# MCU_Circuit.net
KiCad netlist of a schematic drawn in Altium Designer
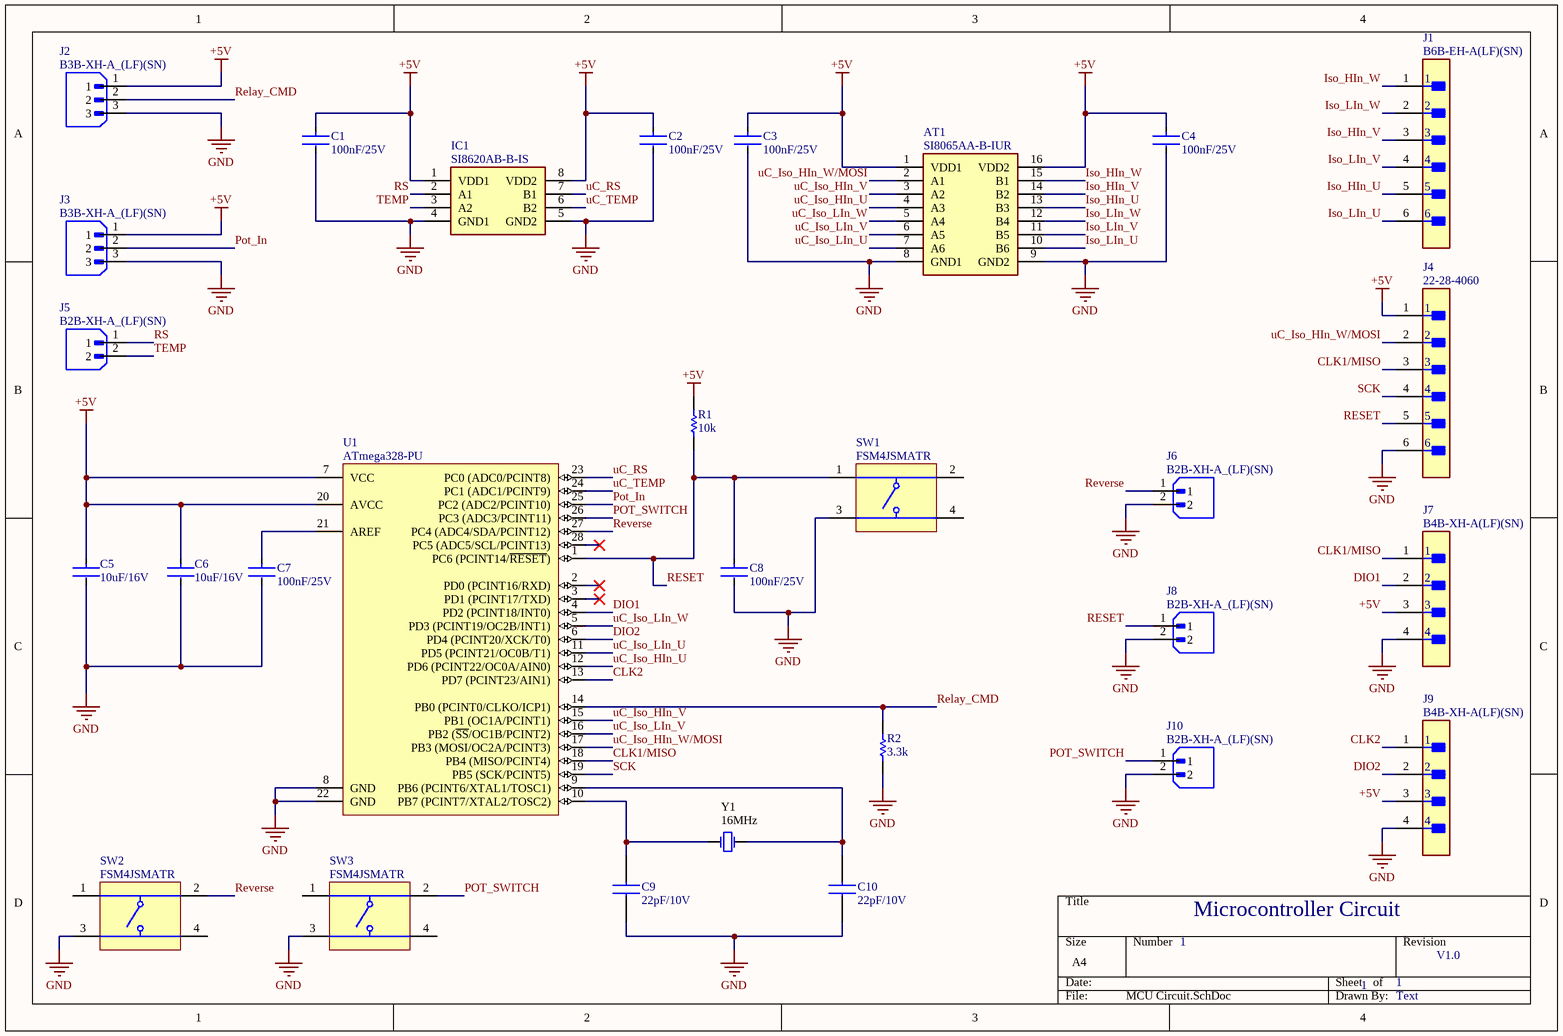
[diagram p0: MCU Circuit.SchDoc]

(export (version "E")
  (design (tool "Eeschema 10.0.6"))
  (components
    (comp (ref "AT1")
      (value "SI8065AA-B-IUR")
      (footprint "SamacSys:SOP64P600X175-16N")
      (description "Attenuator or Isolator")
      (fields (field (name "MOUSER PART NUMBER") "634-SI8065AA-B-IUR"))
      (libsource (lib "*") (part "SI8065AA-B-IUR"))
    )
    (comp (ref "C1")
      (value "100nF/25V")
      (footprint "FP-1210-L_3_3_0_4-W_2_5_0-MFG")
      (description "General Purpose Ceramic Capacitor, 1210, 100nF, 10%, X7R, +15%, 50V")
      (fields (field (name "TOLERANCE") "10%") (field (name "VOLTAGE") "50V"))
      (libsource (lib "Altium Content Vault") (part "b4654b650e69147ec39a6b967a45e02"))
    )
    (comp (ref "C2")
      (value "100nF/25V")
      (footprint "FP-1210-L_3_3_0_4-W_2_5_0-MFG")
      (description "General Purpose Ceramic Capacitor, 1210, 100nF, 10%, X7R, +15%, 50V")
      (fields (field (name "TOLERANCE") "10%") (field (name "VOLTAGE") "50V"))
      (libsource (lib "Altium Content Vault") (part "b4654b650e69147ec39a6b967a45e02"))
    )
    (comp (ref "C3")
      (value "100nF/25V")
      (footprint "FP-1210-L_3_3_0_4-W_2_5_0-MFG")
      (description "General Purpose Ceramic Capacitor, 1210, 100nF, 10%, X7R, +15%, 50V")
      (fields (field (name "TOLERANCE") "10%") (field (name "VOLTAGE") "50V"))
      (libsource (lib "Altium Content Vault") (part "b4654b650e69147ec39a6b967a45e02"))
    )
    (comp (ref "C4")
      (value "100nF/25V")
      (footprint "FP-1210-L_3_3_0_4-W_2_5_0-MFG")
      (description "General Purpose Ceramic Capacitor, 1210, 100nF, 10%, X7R, +15%, 50V")
      (fields (field (name "TOLERANCE") "10%") (field (name "VOLTAGE") "50V"))
      (libsource (lib "Altium Content Vault") (part "b4654b650e69147ec39a6b967a45e02"))
    )
    (comp (ref "C5")
      (value "10uF/16V")
      (footprint "FP-1206-L_3_2_0_2-W_1_6_0-IPC_A")
      (description "General Purpose Ceramic Capacitor, 1206, 10uF, 10%, X5R, 15%, 10V")
      (fields (field (name "TOLERANCE") "10%") (field (name "VOLTAGE") "10V"))
      (libsource (lib "Altium Content Vault") (part "02cd4be3c70576c341d710602a673aa"))
    )
    (comp (ref "C6")
      (value "10uF/16V")
      (footprint "FP-1206-L_3_2_0_2-W_1_6_0-IPC_A")
      (description "General Purpose Ceramic Capacitor, 1206, 10uF, 10%, X5R, 15%, 10V")
      (fields (field (name "TOLERANCE") "10%") (field (name "VOLTAGE") "10V"))
      (libsource (lib "Altium Content Vault") (part "02cd4be3c70576c341d710602a673aa"))
    )
    (comp (ref "C7")
      (value "100nF/25V")
      (footprint "FP-1210-L_3_3_0_4-W_2_5_0-MFG")
      (description "General Purpose Ceramic Capacitor, 1210, 100nF, 10%, X7R, +15%, 50V")
      (fields (field (name "TOLERANCE") "10%") (field (name "VOLTAGE") "50V"))
      (libsource (lib "Altium Content Vault") (part "b4654b650e69147ec39a6b967a45e02"))
    )
    (comp (ref "C8")
      (value "100nF/25V")
      (footprint "FP-1210-L_3_3_0_4-W_2_5_0-MFG")
      (description "General Purpose Ceramic Capacitor, 1210, 100nF, 10%, X7R, +15%, 50V")
      (fields (field (name "TOLERANCE") "10%") (field (name "VOLTAGE") "50V"))
      (libsource (lib "Altium Content Vault") (part "b4654b650e69147ec39a6b967a45e02"))
    )
    (comp (ref "C9")
      (value "22pF/10V")
      (footprint "SamacSys:CAPC3216X90N")
      (description "Capacitor")
      (fields
        (field (name "MANUFACTURER_PART_NUMBER") "885012008002")
        (field (name "MOUSER PART NUMBER") "710-885012008002")
      )
      (libsource (lib "*") (part "885012008002"))
    )
    (comp (ref "C10")
      (value "22pF/10V")
      (footprint "SamacSys:CAPC3216X90N")
      (description "Capacitor")
      (fields
        (field (name "MANUFACTURER_PART_NUMBER") "885012008002")
        (field (name "MOUSER PART NUMBER") "710-885012008002")
      )
      (libsource (lib "*") (part "885012008002"))
    )
    (comp (ref "IC1")
      (value "SI8620AB-B-IS")
      (footprint "SamacSys:SOIC127P600X175-8N")
      (description "Integrated Circuit")
      (fields (field (name "MOUSER PART NUMBER") "634-SI8620AB-B-IS"))
      (libsource (lib "*") (part "SI8620AB-B-IS"))
    )
    (comp (ref "J1")
      (value "B6B-EH-A(LF)(SN)")
      (footprint "FP-B6B-EH-A_LF_SN-MFG")
      (description "CONN HEADER VERT 6POS 2.5MM")
      (libsource (lib "Altium Content Vault") (part "f2cb566baf1c37ab5a3b8e90bbeafd6"))
    )
    (comp (ref "J2")
      (value "B3B-XH-A_(LF)(SN)")
      (footprint "JST_B3B-XH-A (LF)(SN)")
      (description "Connector Header Through Hole 3 position 0.098 (2.50mm)")
      (fields (field (name "MF") "JST Sales America Inc.") (field (name "MP") "B3B-XH-A (LF)(SN)"))
      (libsource (lib "B3B-XH-A__LF__SN_") (part "B3B-XH-A_(LF)(SN)"))
    )
    (comp (ref "J3")
      (value "B3B-XH-A_(LF)(SN)")
      (footprint "JST_B3B-XH-A (LF)(SN)")
      (description "Connector Header Through Hole 3 position 0.098 (2.50mm)")
      (fields (field (name "MF") "JST Sales America Inc.") (field (name "MP") "B3B-XH-A (LF)(SN)"))
      (libsource (lib "B3B-XH-A__LF__SN_") (part "B3B-XH-A_(LF)(SN)"))
    )
    (comp (ref "J4")
      (value "22-28-4060")
      (footprint "FP-22-28-4060-MFG")
      (description "CONN HEADER VERT 6POS 2.54MM")
      (libsource (lib "Altium Content Vault") (part "f2cb566baf1c37ab5a3b8e90bbeafd6"))
    )
    (comp (ref "J5")
      (value "B2B-XH-A_(LF)(SN)")
      (footprint "JST_B2B-XH-A_(LF)(SN)")
      (description "Connector Header Through Hole 2 position 0.098 (2.50mm)")
      (fields (field (name "MF") "JST Sales") (field (name "MP") "B2B-XH-A (LF)(SN)"))
      (libsource (lib "") (part "B2B-XH-A_(LF)(SN)_1"))
    )
    (comp (ref "J6")
      (value "B2B-XH-A_(LF)(SN)")
      (footprint "JST_B2B-XH-A_(LF)(SN)")
      (description "Connector Header Through Hole 2 position 0.098 (2.50mm)")
      (fields (field (name "MF") "JST Sales") (field (name "MP") "B2B-XH-A (LF)(SN)"))
      (libsource (lib "B2B-XH-A__LF__SN_") (part "B2B-XH-A_(LF)(SN)"))
    )
    (comp (ref "J7")
      (value "B4B-XH-A(LF)(SN)")
      (footprint "FP-B4B-XH-A_LF_SN-MFG")
      (description "CONN HEADER VERT 4POS 2.5MM")
      (libsource (lib "Altium Content Vault") (part "299a8cea1bdcbc3624fe62c390fa72c"))
    )
    (comp (ref "J8")
      (value "B2B-XH-A_(LF)(SN)")
      (footprint "JST_B2B-XH-A_(LF)(SN)")
      (description "Connector Header Through Hole 2 position 0.098 (2.50mm)")
      (fields (field (name "MF") "JST Sales") (field (name "MP") "B2B-XH-A (LF)(SN)"))
      (libsource (lib "B2B-XH-A__LF__SN_") (part "B2B-XH-A_(LF)(SN)"))
    )
    (comp (ref "J9")
      (value "B4B-XH-A(LF)(SN)")
      (footprint "FP-B4B-XH-A_LF_SN-MFG")
      (description "CONN HEADER VERT 4POS 2.5MM")
      (libsource (lib "Altium Content Vault") (part "299a8cea1bdcbc3624fe62c390fa72c"))
    )
    (comp (ref "J10")
      (value "B2B-XH-A_(LF)(SN)")
      (footprint "JST_B2B-XH-A_(LF)(SN)")
      (description "Connector Header Through Hole 2 position 0.098 (2.50mm)")
      (fields (field (name "MF") "JST Sales") (field (name "MP") "B2B-XH-A (LF)(SN)"))
      (libsource (lib "B2B-XH-A__LF__SN_") (part "B2B-XH-A_(LF)(SN)"))
    )
    (comp (ref "R1")
      (value "10k")
      (footprint "RESC3225X70X50NL20T20")
      (description "1210")
      (fields (field (name "PART NUMBER") "ERJ-L14KF10CU") (field (name "MANUFACTURER") "Panasonic"))
      (libsource (lib "Altium Content Vault") (part "RES"))
    )
    (comp (ref "R2")
      (value "3.3k")
      (footprint "RESC3225X70X50NL20T20")
      (description "3.3k 0.5W 1210 SMD Resistor")
      (fields (field (name "PART NUMBER") "ERJ-L14KF10CU") (field (name "MANUFACTURER") "Panasonic"))
      (libsource (lib "Altium Content Vault") (part "RES"))
    )
    (comp (ref "SW1")
      (value "FSM4JSMATR")
      (footprint "TECO-FSM4JSMATR_V")
      (description "Micro Miniature Push Button Switch FSM JSM, 50 mA, -35 to 85 degC, 4-Pin SMD, RoHS, Tape and Reel")
      (fields (field (name "MANUFACTURER") "TE Connectivity"))
      (libsource (lib "Altium Content Vault") (part "SW-SPST-4_A"))
    )
    (comp (ref "SW2")
      (value "FSM4JSMATR")
      (footprint "TECO-FSM4JSMATR_V")
      (description "Micro Miniature Push Button Switch FSM JSM, 50 mA, -35 to 85 degC, 4-Pin SMD, RoHS, Tape and Reel")
      (fields (field (name "MANUFACTURER") "TE Connectivity"))
      (libsource (lib "Altium Content Vault") (part "SW-SPST-4_A"))
    )
    (comp (ref "SW3")
      (value "FSM4JSMATR")
      (footprint "TECO-FSM4JSMATR_V")
      (description "Micro Miniature Push Button Switch FSM JSM, 50 mA, -35 to 85 degC, 4-Pin SMD, RoHS, Tape and Reel")
      (fields (field (name "MANUFACTURER") "TE Connectivity"))
      (libsource (lib "Altium Content Vault") (part "SW-SPST-4_A"))
    )
    (comp (ref "U1")
      (value "ATmega328-PU")
      (footprint "28P3")
      (libsource (lib "Altium Content Vault") (part "MC-8B-ATM48-IL28"))
    )
    (comp (ref "Y1")
      (value "16MHz")
      (footprint "FOX-FOXSLF160-20")
      (description "Resistance Weld Thru-Hole Crystal, 16 MHz, -20 to 70 degC, 2-Pin THD, RoHS, Bulk")
      (fields (field (name "TOLERANCE") "1%"))
      (libsource (lib "Altium Content Vault") (part "XTAL-1-2-2"))
    )
  )
  (nets
    (net (code "1") (name "+5V") (class "Default")
      (node (ref "AT1") (pin "1") (pinfunction "VDD1_1") (pintype "passive"))
      (node (ref "AT1") (pin "16") (pinfunction "VDD2_16") (pintype "passive"))
      (node (ref "C1") (pin "1") (pinfunction "1_1") (pintype "passive"))
      (node (ref "C2") (pin "1") (pinfunction "1_1") (pintype "passive"))
      (node (ref "C3") (pin "1") (pinfunction "1_1") (pintype "passive"))
      (node (ref "C4") (pin "1") (pinfunction "1_1") (pintype "passive"))
      (node (ref "C5") (pin "1") (pinfunction "1_1") (pintype "passive"))
      (node (ref "C6") (pin "1") (pinfunction "1_1") (pintype "passive"))
      (node (ref "IC1") (pin "1") (pinfunction "VDD1_1") (pintype "passive"))
      (node (ref "IC1") (pin "8") (pinfunction "VDD2_8") (pintype "passive"))
      (node (ref "J2") (pin "1") (pinfunction "1_1") (pintype "passive"))
      (node (ref "J3") (pin "1") (pinfunction "1_1") (pintype "passive"))
      (node (ref "J4") (pin "1") (pinfunction "1_1") (pintype "passive"))
      (node (ref "J7") (pin "3") (pinfunction "3_3") (pintype "passive"))
      (node (ref "J9") (pin "3") (pinfunction "3_3") (pintype "passive"))
      (node (ref "R1") (pin "2") (pinfunction "2_2") (pintype "passive"))
      (node (ref "U1") (pin "20") (pinfunction "AVCC_20") (pintype "power_in"))
      (node (ref "U1") (pin "7") (pinfunction "VCC_7") (pintype "power_in"))
    )
    (net (code "2") (name "/CLK1{slash}MISO") (class "Default")
      (node (ref "J4") (pin "3") (pinfunction "3_3") (pintype "passive"))
      (node (ref "J7") (pin "1") (pinfunction "1_1") (pintype "passive"))
      (node (ref "U1") (pin "18") (pinfunction "PB4_(MISO/PCINT4)_18") (pintype "bidirectional"))
    )
    (net (code "3") (name "/CLK2") (class "Default")
      (node (ref "J9") (pin "1") (pinfunction "1_1") (pintype "passive"))
      (node (ref "U1") (pin "13") (pinfunction "PD7_(PCINT23/AIN1)_13") (pintype "bidirectional"))
    )
    (net (code "4") (name "/DIO1") (class "Default")
      (node (ref "J7") (pin "2") (pinfunction "2_2") (pintype "passive"))
      (node (ref "U1") (pin "4") (pinfunction "PD2_(PCINT18/INT0)_4") (pintype "bidirectional"))
    )
    (net (code "5") (name "/DIO2") (class "Default")
      (node (ref "J9") (pin "2") (pinfunction "2_2") (pintype "passive"))
      (node (ref "U1") (pin "6") (pinfunction "PD4_(PCINT20/XCK/T0)_6") (pintype "bidirectional"))
    )
    (net (code "6") (name "/Iso_HIn_U") (class "Default")
      (node (ref "AT1") (pin "13") (pinfunction "B3_13") (pintype "passive"))
      (node (ref "J1") (pin "5") (pinfunction "5_5") (pintype "passive"))
    )
    (net (code "7") (name "/Iso_HIn_V") (class "Default")
      (node (ref "AT1") (pin "14") (pinfunction "B2_14") (pintype "passive"))
      (node (ref "J1") (pin "3") (pinfunction "3_3") (pintype "passive"))
    )
    (net (code "8") (name "/Iso_HIn_W") (class "Default")
      (node (ref "AT1") (pin "15") (pinfunction "B1_15") (pintype "passive"))
      (node (ref "J1") (pin "1") (pinfunction "1_1") (pintype "passive"))
    )
    (net (code "9") (name "/Iso_LIn_U") (class "Default")
      (node (ref "AT1") (pin "10") (pinfunction "B6_10") (pintype "passive"))
      (node (ref "J1") (pin "6") (pinfunction "6_6") (pintype "passive"))
    )
    (net (code "10") (name "/Iso_LIn_V") (class "Default")
      (node (ref "AT1") (pin "11") (pinfunction "B5_11") (pintype "passive"))
      (node (ref "J1") (pin "4") (pinfunction "4_4") (pintype "passive"))
    )
    (net (code "11") (name "/Iso_LIn_W") (class "Default")
      (node (ref "AT1") (pin "12") (pinfunction "B4_12") (pintype "passive"))
      (node (ref "J1") (pin "2") (pinfunction "2_2") (pintype "passive"))
    )
    (net (code "12") (name "/POT_SWITCH") (class "Default")
      (node (ref "J10") (pin "1") (pinfunction "1_1") (pintype "passive"))
      (node (ref "SW3") (pin "2") (pinfunction "2_2") (pintype "passive"))
      (node (ref "U1") (pin "26") (pinfunction "PC3_(ADC3/PCINT11)_26") (pintype "bidirectional"))
    )
    (net (code "13") (name "/Pot_In") (class "Default")
      (node (ref "J3") (pin "2") (pinfunction "2_2") (pintype "passive"))
      (node (ref "U1") (pin "25") (pinfunction "PC2_(ADC2/PCINT10)_25") (pintype "bidirectional"))
    )
    (net (code "14") (name "/RESET") (class "Default")
      (node (ref "C8") (pin "1") (pinfunction "1_1") (pintype "passive"))
      (node (ref "J4") (pin "5") (pinfunction "5_5") (pintype "passive"))
      (node (ref "J8") (pin "1") (pinfunction "1_1") (pintype "passive"))
      (node (ref "R1") (pin "1") (pinfunction "1_1") (pintype "passive"))
      (node (ref "SW1") (pin "1") (pinfunction "1_1") (pintype "passive"))
      (node (ref "U1") (pin "1") (pinfunction "PC6_(PCINT14/~{RESET})_1") (pintype "bidirectional"))
    )
    (net (code "15") (name "/RS") (class "Default")
      (node (ref "IC1") (pin "2") (pinfunction "A1_2") (pintype "passive"))
      (node (ref "J5") (pin "1") (pinfunction "1_1") (pintype "passive"))
    )
    (net (code "16") (name "/Relay_CMD") (class "Default")
      (node (ref "J2") (pin "2") (pinfunction "2_2") (pintype "passive"))
      (node (ref "R2") (pin "2") (pinfunction "2_2") (pintype "passive"))
      (node (ref "U1") (pin "14") (pinfunction "PB0_(PCINT0/CLKO/ICP1)_14") (pintype "bidirectional"))
    )
    (net (code "17") (name "/Reverse") (class "Default")
      (node (ref "J6") (pin "1") (pinfunction "1_1") (pintype "passive"))
      (node (ref "SW2") (pin "2") (pinfunction "2_2") (pintype "passive"))
      (node (ref "U1") (pin "27") (pinfunction "PC4_(ADC4/SDA/PCINT12)_27") (pintype "bidirectional"))
    )
    (net (code "18") (name "/SCK") (class "Default")
      (node (ref "J4") (pin "4") (pinfunction "4_4") (pintype "passive"))
      (node (ref "U1") (pin "19") (pinfunction "PB5_(SCK/PCINT5)_19") (pintype "bidirectional"))
    )
    (net (code "19") (name "/TEMP") (class "Default")
      (node (ref "IC1") (pin "3") (pinfunction "A2_3") (pintype "passive"))
      (node (ref "J5") (pin "2") (pinfunction "2_2") (pintype "passive"))
    )
    (net (code "20") (name "/uC_Iso_HIn_U") (class "Default")
      (node (ref "AT1") (pin "4") (pinfunction "A3_4") (pintype "passive"))
      (node (ref "U1") (pin "12") (pinfunction "PD6_(PCINT22/OC0A/AIN0)_12") (pintype "bidirectional"))
    )
    (net (code "21") (name "/uC_Iso_HIn_V") (class "Default")
      (node (ref "AT1") (pin "3") (pinfunction "A2_3") (pintype "passive"))
      (node (ref "U1") (pin "15") (pinfunction "PB1_(OC1A/PCINT1)_15") (pintype "bidirectional"))
    )
    (net (code "22") (name "/uC_Iso_HIn_W{slash}MOSI") (class "Default")
      (node (ref "AT1") (pin "2") (pinfunction "A1_2") (pintype "passive"))
      (node (ref "J4") (pin "2") (pinfunction "2_2") (pintype "passive"))
      (node (ref "U1") (pin "17") (pinfunction "PB3_(MOSI/OC2A/PCINT3)_17") (pintype "bidirectional"))
    )
    (net (code "23") (name "/uC_Iso_LIn_U") (class "Default")
      (node (ref "AT1") (pin "7") (pinfunction "A6_7") (pintype "passive"))
      (node (ref "U1") (pin "11") (pinfunction "PD5_(PCINT21/OC0B/T1)_11") (pintype "bidirectional"))
    )
    (net (code "24") (name "/uC_Iso_LIn_V") (class "Default")
      (node (ref "AT1") (pin "6") (pinfunction "A5_6") (pintype "passive"))
      (node (ref "U1") (pin "16") (pinfunction "PB2_(~{SS}/OC1B/PCINT2)_16") (pintype "bidirectional"))
    )
    (net (code "25") (name "/uC_Iso_LIn_W") (class "Default")
      (node (ref "AT1") (pin "5") (pinfunction "A4_5") (pintype "passive"))
      (node (ref "U1") (pin "5") (pinfunction "PD3_(PCINT19/OC2B/INT1)_5") (pintype "bidirectional"))
    )
    (net (code "26") (name "/uC_RS") (class "Default")
      (node (ref "IC1") (pin "7") (pinfunction "B1_7") (pintype "passive"))
      (node (ref "U1") (pin "23") (pinfunction "PC0_(ADC0/PCINT8)_23") (pintype "bidirectional"))
    )
    (net (code "27") (name "/uC_TEMP") (class "Default")
      (node (ref "IC1") (pin "6") (pinfunction "B2_6") (pintype "passive"))
      (node (ref "U1") (pin "24") (pinfunction "PC1_(ADC1/PCINT9)_24") (pintype "bidirectional"))
    )
    (net (code "28") (name "GND") (class "Default")
      (node (ref "AT1") (pin "8") (pinfunction "GND1_8") (pintype "passive"))
      (node (ref "AT1") (pin "9") (pinfunction "GND2_9") (pintype "passive"))
      (node (ref "C1") (pin "2") (pinfunction "2_2") (pintype "passive"))
      (node (ref "C10") (pin "1") (pinfunction "1_1") (pintype "passive"))
      (node (ref "C2") (pin "2") (pinfunction "2_2") (pintype "passive"))
      (node (ref "C3") (pin "2") (pinfunction "2_2") (pintype "passive"))
      (node (ref "C4") (pin "2") (pinfunction "2_2") (pintype "passive"))
      (node (ref "C5") (pin "2") (pinfunction "2_2") (pintype "passive"))
      (node (ref "C6") (pin "2") (pinfunction "2_2") (pintype "passive"))
      (node (ref "C7") (pin "2") (pinfunction "2_2") (pintype "passive"))
      (node (ref "C8") (pin "2") (pinfunction "2_2") (pintype "passive"))
      (node (ref "C9") (pin "1") (pinfunction "1_1") (pintype "passive"))
      (node (ref "IC1") (pin "4") (pinfunction "GND1_4") (pintype "passive"))
      (node (ref "IC1") (pin "5") (pinfunction "GND2_5") (pintype "passive"))
      (node (ref "J10") (pin "2") (pinfunction "2_2") (pintype "passive"))
      (node (ref "J2") (pin "3") (pinfunction "3_3") (pintype "passive"))
      (node (ref "J3") (pin "3") (pinfunction "3_3") (pintype "passive"))
      (node (ref "J4") (pin "6") (pinfunction "6_6") (pintype "passive"))
      (node (ref "J6") (pin "2") (pinfunction "2_2") (pintype "passive"))
      (node (ref "J7") (pin "4") (pinfunction "4_4") (pintype "passive"))
      (node (ref "J8") (pin "2") (pinfunction "2_2") (pintype "passive"))
      (node (ref "J9") (pin "4") (pinfunction "4_4") (pintype "passive"))
      (node (ref "R2") (pin "1") (pinfunction "1_1") (pintype "passive"))
      (node (ref "SW1") (pin "3") (pinfunction "3_3") (pintype "passive"))
      (node (ref "SW2") (pin "3") (pinfunction "3_3") (pintype "passive"))
      (node (ref "SW3") (pin "3") (pinfunction "3_3") (pintype "passive"))
      (node (ref "U1") (pin "22") (pinfunction "GND_22") (pintype "power_in"))
      (node (ref "U1") (pin "8") (pinfunction "GND_8") (pintype "power_in"))
    )
    (net (code "29") (name "Net-(U1-AREF)") (class "Default")
      (node (ref "C7") (pin "1") (pinfunction "1_1") (pintype "passive"))
      (node (ref "U1") (pin "21") (pinfunction "AREF_21") (pintype "power_in"))
    )
    (net (code "30") (name "Net-(U1-PB6_(PCINT6{slash}XTAL1{slash}TOSC1))") (class "Default")
      (node (ref "C10") (pin "2") (pinfunction "2_2") (pintype "passive"))
      (node (ref "U1") (pin "9") (pinfunction "PB6_(PCINT6/XTAL1/TOSC1)_9") (pintype "bidirectional"))
      (node (ref "Y1") (pin "2") (pinfunction "2_2") (pintype "passive"))
    )
    (net (code "31") (name "Net-(U1-PB7_(PCINT7{slash}XTAL2{slash}TOSC2))") (class "Default")
      (node (ref "C9") (pin "2") (pinfunction "2_2") (pintype "passive"))
      (node (ref "U1") (pin "10") (pinfunction "PB7_(PCINT7/XTAL2/TOSC2)_10") (pintype "bidirectional"))
      (node (ref "Y1") (pin "1") (pinfunction "1_1") (pintype "passive"))
    )
    (net (code "32") (name "unconnected-(SW1-Pad2)") (class "Default")
      (node (ref "SW1") (pin "2") (pinfunction "2_2") (pintype "passive"))
    )
    (net (code "33") (name "unconnected-(SW1-Pad4)") (class "Default")
      (node (ref "SW1") (pin "4") (pinfunction "4_4") (pintype "passive"))
    )
    (net (code "34") (name "unconnected-(SW2-Pad1)") (class "Default")
      (node (ref "SW2") (pin "1") (pinfunction "1_1") (pintype "passive"))
    )
    (net (code "35") (name "unconnected-(SW2-Pad4)") (class "Default")
      (node (ref "SW2") (pin "4") (pinfunction "4_4") (pintype "passive"))
    )
    (net (code "36") (name "unconnected-(SW3-Pad1)") (class "Default")
      (node (ref "SW3") (pin "1") (pinfunction "1_1") (pintype "passive"))
    )
    (net (code "37") (name "unconnected-(SW3-Pad4)") (class "Default")
      (node (ref "SW3") (pin "4") (pinfunction "4_4") (pintype "passive"))
    )
    (net (code "38") (name "unconnected-(U1-PC5_(ADC5{slash}SCL{slash}PCINT13)-Pad28)") (class "Default")
      (node (ref "U1") (pin "28") (pinfunction "PC5_(ADC5/SCL/PCINT13)_28") (pintype "bidirectional+no_connect"))
    )
    (net (code "39") (name "unconnected-(U1-PD0_(PCINT16{slash}RXD)-Pad2)") (class "Default")
      (node (ref "U1") (pin "2") (pinfunction "PD0_(PCINT16/RXD)_2") (pintype "bidirectional+no_connect"))
    )
    (net (code "40") (name "unconnected-(U1-PD1_(PCINT17{slash}TXD)-Pad3)") (class "Default")
      (node (ref "U1") (pin "3") (pinfunction "PD1_(PCINT17/TXD)_3") (pintype "bidirectional+no_connect"))
    )
  )
)
